# Microcontroller.net
KiCad netlist of a schematic drawn in Altium Designer
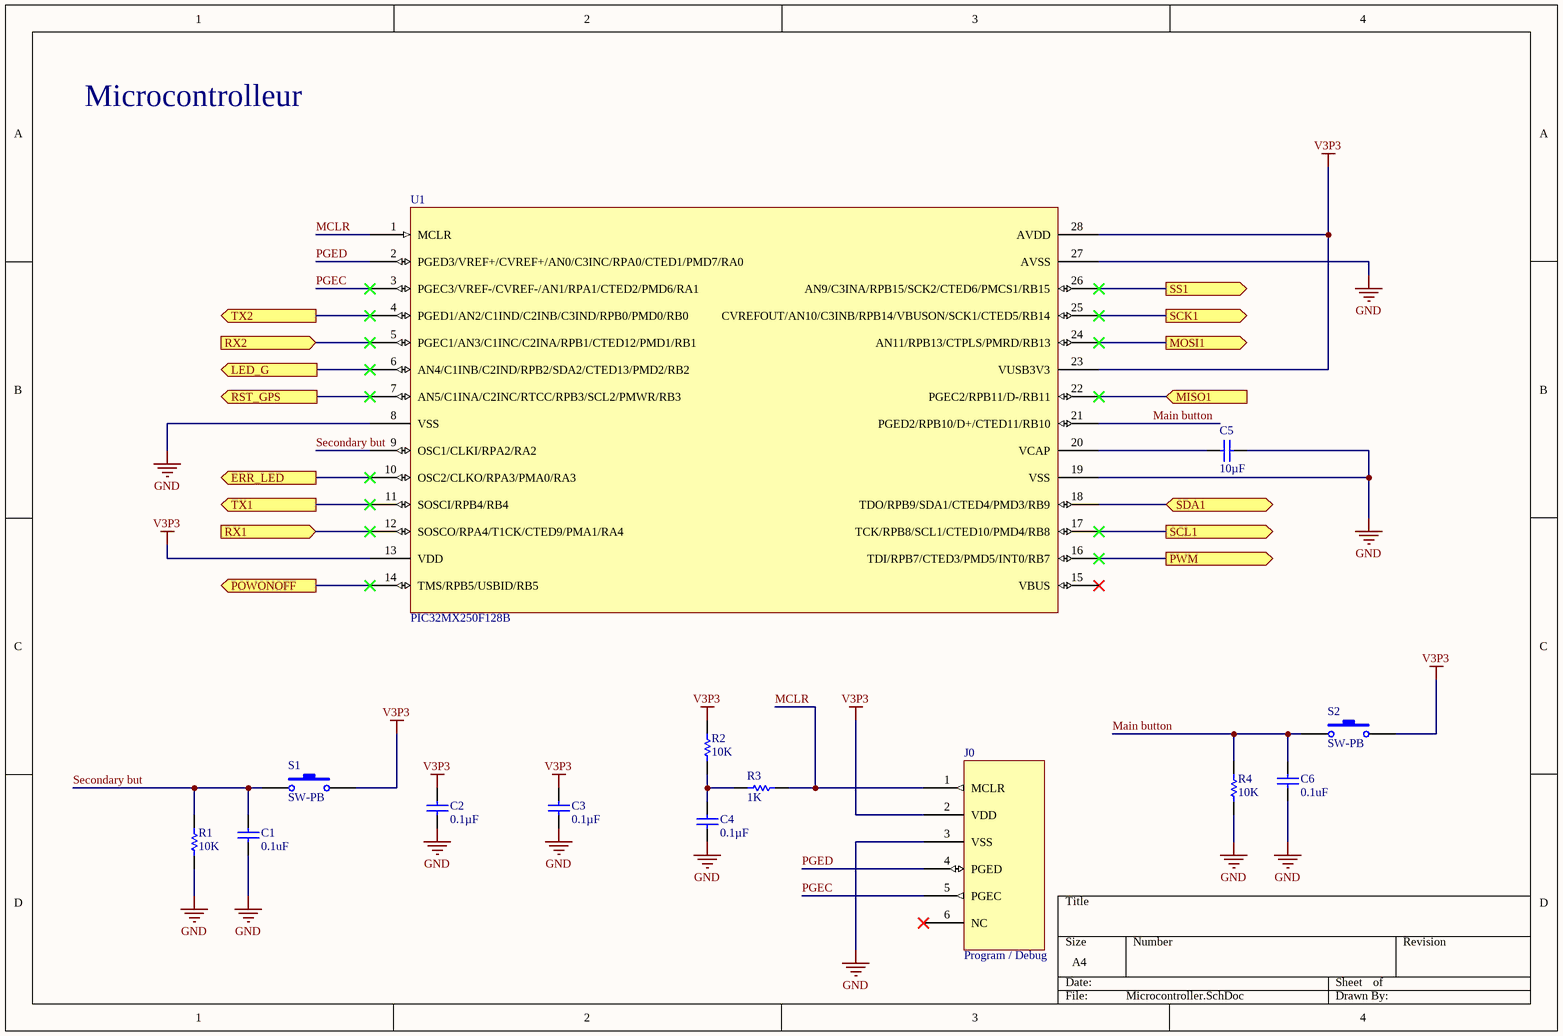
[diagram p0: Microcontroller.SchDoc]

(export (version "E")
  (design (tool "Eeschema 10.0.6"))
  (components
    (comp (ref "C1")
      (value "0.1uF")
      (footprint "own_0603")
      (description "Capacitor")
      (libsource (lib "Miscellaneous Devices") (part "Cap"))
    )
    (comp (ref "C2")
      (value "0.1µF")
      (footprint "own_0603")
      (description "Capacitor")
      (libsource (lib "Miscellaneous Devices") (part "Cap"))
    )
    (comp (ref "C3")
      (value "0.1µF")
      (footprint "own_0603")
      (description "Capacitor")
      (libsource (lib "Miscellaneous Devices") (part "Cap"))
    )
    (comp (ref "C4")
      (value "0.1µF")
      (footprint "own_0603")
      (description "Capacitor")
      (libsource (lib "Miscellaneous Devices") (part "Cap"))
    )
    (comp (ref "C5")
      (value "10µF")
      (footprint "own_0603")
      (description "Capacitor")
      (libsource (lib "Miscellaneous Devices") (part "Cap"))
    )
    (comp (ref "C6")
      (value "0.1uF")
      (footprint "own_0603")
      (description "Capacitor")
      (libsource (lib "Miscellaneous Devices") (part "Cap"))
    )
    (comp (ref "J0")
      (value "Program / Debug")
      (footprint "C-Grid III X6")
      (libsource (lib "Schlib") (part "ICSP"))
    )
    (comp (ref "R1")
      (value "10K")
      (footprint "own_0603")
      (description "Resistor")
      (libsource (lib "Miscellaneous Devices") (part "Res1"))
    )
    (comp (ref "R2")
      (value "10K")
      (footprint "own_0603")
      (description "Resistor")
      (libsource (lib "Miscellaneous Devices") (part "Res1"))
    )
    (comp (ref "R3")
      (value "1K")
      (footprint "own_0603")
      (description "Resistor")
      (libsource (lib "Miscellaneous Devices") (part "Res1"))
    )
    (comp (ref "R4")
      (value "10K")
      (footprint "own_0603")
      (description "Resistor")
      (libsource (lib "Miscellaneous Devices") (part "Res1"))
    )
    (comp (ref "S1")
      (value "SW-PB")
      (footprint "SWTCH 1")
      (description "Switch")
      (libsource (lib "Miscellaneous Devices") (part "SW-PB"))
    )
    (comp (ref "S2")
      (value "SW-PB")
      (footprint "SWTCH 1")
      (description "Switch")
      (libsource (lib "Miscellaneous Devices") (part "SW-PB"))
    )
    (comp (ref "U1")
      (value "PIC32MX250F128B")
      (footprint "PIC32MX250F128/SO")
      (description "Microcontrolleur")
      (libsource (lib "Schlib") (part "PIC32MX250F128B"))
    )
  )
  (nets
    (net (code "1") (name "/ERR_LED") (class "Default")
      (node (ref "U1") (pin "10") (pinfunction "OSC2/CLKO/RPA3/PMA0/RA3_10") (pintype "bidirectional+no_connect"))
    )
    (net (code "2") (name "/LED_G") (class "Default")
      (node (ref "U1") (pin "6") (pinfunction "AN4/C1INB/C2IND/RPB2/SDA2/CTED13/PMD2/RB2_6") (pintype "bidirectional+no_connect"))
    )
    (net (code "3") (name "/MCLR") (class "Default")
      (node (ref "J0") (pin "1") (pinfunction "MCLR_1") (pintype "output"))
      (node (ref "R3") (pin "2") (pinfunction "2_2") (pintype "passive"))
      (node (ref "U1") (pin "1") (pinfunction "MCLR_1") (pintype "input"))
    )
    (net (code "4") (name "/MISO1") (class "Default")
      (node (ref "U1") (pin "22") (pinfunction "PGEC2/RPB11/D-/RB11_22") (pintype "bidirectional+no_connect"))
    )
    (net (code "5") (name "/MOSI1") (class "Default")
      (node (ref "U1") (pin "24") (pinfunction "AN11/RPB13/CTPLS/PMRD/RB13_24") (pintype "bidirectional+no_connect"))
    )
    (net (code "6") (name "/Main button") (class "Default")
      (node (ref "C6") (pin "2") (pinfunction "2_2") (pintype "passive"))
      (node (ref "R4") (pin "2") (pinfunction "2_2") (pintype "passive"))
      (node (ref "S2") (pin "1") (pinfunction "1_1") (pintype "passive"))
      (node (ref "U1") (pin "21") (pinfunction "PGED2/RPB10/D+/CTED11/RB10_21") (pintype "bidirectional"))
    )
    (net (code "7") (name "/PGEC") (class "Default")
      (node (ref "J0") (pin "5") (pinfunction "PGEC_5") (pintype "output"))
      (node (ref "U1") (pin "3") (pinfunction "PGEC3/VREF-/CVREF-/AN1/RPA1/CTED2/PMD6/RA1_3") (pintype "bidirectional"))
    )
    (net (code "8") (name "/PGED") (class "Default")
      (node (ref "J0") (pin "4") (pinfunction "PGED_4") (pintype "bidirectional"))
      (node (ref "U1") (pin "2") (pinfunction "PGED3/VREF+/CVREF+/AN0/C3INC/RPA0/CTED1/PMD7/RA0_2") (pintype "bidirectional"))
    )
    (net (code "9") (name "/POWONOFF") (class "Default")
      (node (ref "U1") (pin "14") (pinfunction "TMS/RPB5/USBID/RB5_14") (pintype "bidirectional+no_connect"))
    )
    (net (code "10") (name "/PWM") (class "Default")
      (node (ref "U1") (pin "16") (pinfunction "TDI/RPB7/CTED3/PMD5/INT0/RB7_16") (pintype "bidirectional+no_connect"))
    )
    (net (code "11") (name "/RST_GPS") (class "Default")
      (node (ref "U1") (pin "7") (pinfunction "AN5/C1INA/C2INC/RTCC/RPB3/SCL2/PMWR/RB3_7") (pintype "bidirectional+no_connect"))
    )
    (net (code "12") (name "/RX1") (class "Default")
      (node (ref "U1") (pin "12") (pinfunction "SOSCO/RPA4/T1CK/CTED9/PMA1/RA4_12") (pintype "bidirectional+no_connect"))
    )
    (net (code "13") (name "/RX2") (class "Default")
      (node (ref "U1") (pin "5") (pinfunction "PGEC1/AN3/C1INC/C2INA/RPB1/CTED12/PMD1/RB1_5") (pintype "bidirectional+no_connect"))
    )
    (net (code "14") (name "/SCK1") (class "Default")
      (node (ref "U1") (pin "25") (pinfunction "CVREFOUT/AN10/C3INB/RPB14/VBUSON/SCK1/CTED5/RB14_25") (pintype "bidirectional+no_connect"))
    )
    (net (code "15") (name "/SCL1") (class "Default")
      (node (ref "U1") (pin "17") (pinfunction "TCK/RPB8/SCL1/CTED10/PMD4/RB8_17") (pintype "bidirectional+no_connect"))
    )
    (net (code "16") (name "/SDA1") (class "Default")
      (node (ref "U1") (pin "18") (pinfunction "TDO/RPB9/SDA1/CTED4/PMD3/RB9_18") (pintype "bidirectional"))
    )
    (net (code "17") (name "/SS1") (class "Default")
      (node (ref "U1") (pin "26") (pinfunction "AN9/C3INA/RPB15/SCK2/CTED6/PMCS1/RB15_26") (pintype "bidirectional+no_connect"))
    )
    (net (code "18") (name "/Secondary but") (class "Default")
      (node (ref "C1") (pin "2") (pinfunction "2_2") (pintype "passive"))
      (node (ref "R1") (pin "2") (pinfunction "2_2") (pintype "passive"))
      (node (ref "S1") (pin "1") (pinfunction "1_1") (pintype "passive"))
      (node (ref "U1") (pin "9") (pinfunction "OSC1/CLKI/RPA2/RA2_9") (pintype "bidirectional"))
    )
    (net (code "19") (name "/TX1") (class "Default")
      (node (ref "U1") (pin "11") (pinfunction "SOSCI/RPB4/RB4_11") (pintype "bidirectional+no_connect"))
    )
    (net (code "20") (name "/TX2") (class "Default")
      (node (ref "U1") (pin "4") (pinfunction "PGED1/AN2/C1IND/C2INB/C3IND/RPB0/PMD0/RB0_4") (pintype "bidirectional+no_connect"))
    )
    (net (code "21") (name "GND") (class "Default")
      (node (ref "C1") (pin "1") (pinfunction "1_1") (pintype "passive"))
      (node (ref "C2") (pin "1") (pinfunction "1_1") (pintype "passive"))
      (node (ref "C3") (pin "1") (pinfunction "1_1") (pintype "passive"))
      (node (ref "C4") (pin "1") (pinfunction "1_1") (pintype "passive"))
      (node (ref "C5") (pin "1") (pinfunction "1_1") (pintype "passive"))
      (node (ref "C6") (pin "1") (pinfunction "1_1") (pintype "passive"))
      (node (ref "J0") (pin "3") (pinfunction "VSS_3") (pintype "power_in"))
      (node (ref "R1") (pin "1") (pinfunction "1_1") (pintype "passive"))
      (node (ref "R4") (pin "1") (pinfunction "1_1") (pintype "passive"))
      (node (ref "U1") (pin "19") (pinfunction "VSS_19") (pintype "power_in"))
      (node (ref "U1") (pin "27") (pinfunction "AVSS_27") (pintype "power_in"))
      (node (ref "U1") (pin "8") (pinfunction "VSS_8") (pintype "power_in"))
    )
    (net (code "22") (name "Net-(C4-Pad2)") (class "Default")
      (node (ref "C4") (pin "2") (pinfunction "2_2") (pintype "passive"))
      (node (ref "R2") (pin "1") (pinfunction "1_1") (pintype "passive"))
      (node (ref "R3") (pin "1") (pinfunction "1_1") (pintype "passive"))
    )
    (net (code "23") (name "Net-(U1-VCAP)") (class "Default")
      (node (ref "C5") (pin "2") (pinfunction "2_2") (pintype "passive"))
      (node (ref "U1") (pin "20") (pinfunction "VCAP_20") (pintype "power_in"))
    )
    (net (code "24") (name "V3P3") (class "Default")
      (node (ref "C2") (pin "2") (pinfunction "2_2") (pintype "passive"))
      (node (ref "C3") (pin "2") (pinfunction "2_2") (pintype "passive"))
      (node (ref "J0") (pin "2") (pinfunction "VDD_2") (pintype "power_in"))
      (node (ref "R2") (pin "2") (pinfunction "2_2") (pintype "passive"))
      (node (ref "S1") (pin "2") (pinfunction "2_2") (pintype "passive"))
      (node (ref "S2") (pin "2") (pinfunction "2_2") (pintype "passive"))
      (node (ref "U1") (pin "13") (pinfunction "VDD_13") (pintype "passive"))
      (node (ref "U1") (pin "23") (pinfunction "VUSB3V3_23") (pintype "power_in"))
      (node (ref "U1") (pin "28") (pinfunction "AVDD_28") (pintype "power_in"))
    )
    (net (code "25") (name "unconnected-(J0-NC-Pad6)") (class "Default")
      (node (ref "J0") (pin "6") (pinfunction "NC_6") (pintype "passive+no_connect"))
    )
    (net (code "26") (name "unconnected-(U1-VBUS-Pad15)") (class "Default")
      (node (ref "U1") (pin "15") (pinfunction "VBUS_15") (pintype "bidirectional+no_connect"))
    )
  )
)
